# L_B_block_base.net
KiCad netlist of a schematic drawn in EAGLE
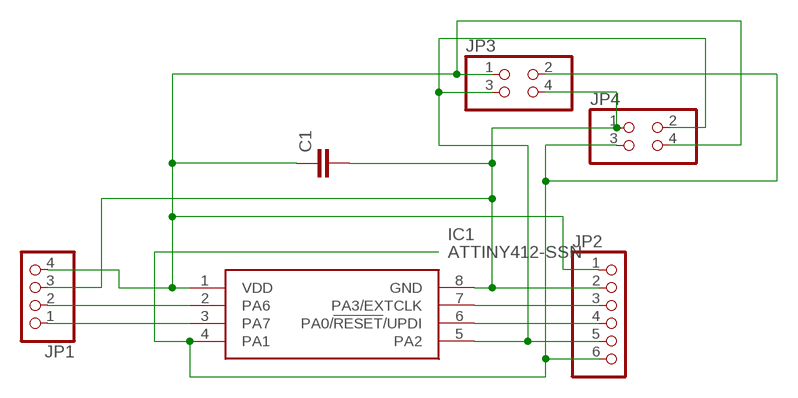
[diagram p0: schematic, sheet 1]

(export (version "E")
  (design (tool "Eeschema 10.0.6"))
  (components
    (comp (ref "C1")
      (value "C-EUC0805K")
      (footprint "eagle-import:C0805K")
      (libsource (lib "eagle-import") (part "C-EUC0805K"))
    )
    (comp (ref "IC1")
      (value "ATTINY412-SSN")
      (footprint "eagle-import:SOIC127P600X175-8N")
      (fields (field (name "MOUSER_PART_NUMBER") "579-ATTINY412-SSN"))
      (libsource (lib "eagle-import") (part "ATTINY412-SSN"))
    )
    (comp (ref "JP1")
      (value "PINHD-1X4")
      (footprint "eagle-import:1X04")
      (libsource (lib "eagle-import") (part "PINHD-1X4"))
    )
    (comp (ref "JP2")
      (value "PINHD-1X6")
      (footprint "eagle-import:1X06")
      (libsource (lib "eagle-import") (part "PINHD-1X6"))
    )
    (comp (ref "JP3")
      (value "PINHD-2X2")
      (footprint "eagle-import:2X02")
      (libsource (lib "eagle-import") (part "PINHD-2X2"))
    )
    (comp (ref "JP4")
      (value "PINHD-2X2")
      (footprint "eagle-import:2X02")
      (libsource (lib "eagle-import") (part "PINHD-2X2"))
    )
  )
  (nets
    (net (code "1") (name "Net-(IC1-GND)") (class "Default")
      (node (ref "C1") (pin "2") (pinfunction "2_2") (pintype "passive"))
      (node (ref "IC1") (pin "8") (pinfunction "GND_8") (pintype "bidirectional"))
      (node (ref "JP1") (pin "3") (pinfunction "3_3") (pintype "passive"))
      (node (ref "JP2") (pin "2") (pinfunction "2_2") (pintype "passive"))
      (node (ref "JP3") (pin "4") (pinfunction "4_4") (pintype "passive"))
      (node (ref "JP4") (pin "1") (pinfunction "1_1") (pintype "passive"))
    )
    (net (code "2") (name "Net-(IC1-PA0{slash}~{RESET}{slash}UPDI)") (class "Default")
      (node (ref "IC1") (pin "6") (pinfunction "PA0/~{RESET}/UPDI_6") (pintype "bidirectional"))
      (node (ref "JP2") (pin "4") (pinfunction "4_4") (pintype "passive"))
    )
    (net (code "3") (name "Net-(IC1-PA1)") (class "Default")
      (node (ref "IC1") (pin "4") (pinfunction "PA1_4") (pintype "bidirectional"))
      (node (ref "JP2") (pin "6") (pinfunction "6_6") (pintype "passive"))
      (node (ref "JP3") (pin "2") (pinfunction "2_2") (pintype "passive"))
      (node (ref "JP4") (pin "3") (pinfunction "3_3") (pintype "passive"))
    )
    (net (code "4") (name "Net-(IC1-PA2)") (class "Default")
      (node (ref "IC1") (pin "5") (pinfunction "PA2_5") (pintype "bidirectional"))
      (node (ref "JP2") (pin "5") (pinfunction "5_5") (pintype "passive"))
      (node (ref "JP3") (pin "3") (pinfunction "3_3") (pintype "passive"))
      (node (ref "JP4") (pin "2") (pinfunction "2_2") (pintype "passive"))
    )
    (net (code "5") (name "Net-(IC1-PA3{slash}EXTCLK)") (class "Default")
      (node (ref "IC1") (pin "7") (pinfunction "PA3/EXTCLK_7") (pintype "bidirectional"))
      (node (ref "JP2") (pin "3") (pinfunction "3_3") (pintype "passive"))
    )
    (net (code "6") (name "Net-(IC1-PA6)") (class "Default")
      (node (ref "IC1") (pin "2") (pinfunction "PA6_2") (pintype "bidirectional"))
      (node (ref "JP1") (pin "2") (pinfunction "2_2") (pintype "passive"))
    )
    (net (code "7") (name "Net-(IC1-PA7)") (class "Default")
      (node (ref "IC1") (pin "3") (pinfunction "PA7_3") (pintype "bidirectional"))
      (node (ref "JP1") (pin "1") (pinfunction "1_1") (pintype "passive"))
    )
    (net (code "8") (name "Net-(IC1-VDD)") (class "Default")
      (node (ref "C1") (pin "1") (pinfunction "1_1") (pintype "passive"))
      (node (ref "IC1") (pin "1") (pinfunction "VDD_1") (pintype "bidirectional"))
      (node (ref "JP1") (pin "4") (pinfunction "4_4") (pintype "passive"))
      (node (ref "JP2") (pin "1") (pinfunction "1_1") (pintype "passive"))
      (node (ref "JP3") (pin "1") (pinfunction "1_1") (pintype "passive"))
      (node (ref "JP4") (pin "4") (pinfunction "4_4") (pintype "passive"))
    )
  )
)
